# shared_pcb.net
KiCad netlist of a schematic drawn in EAGLE
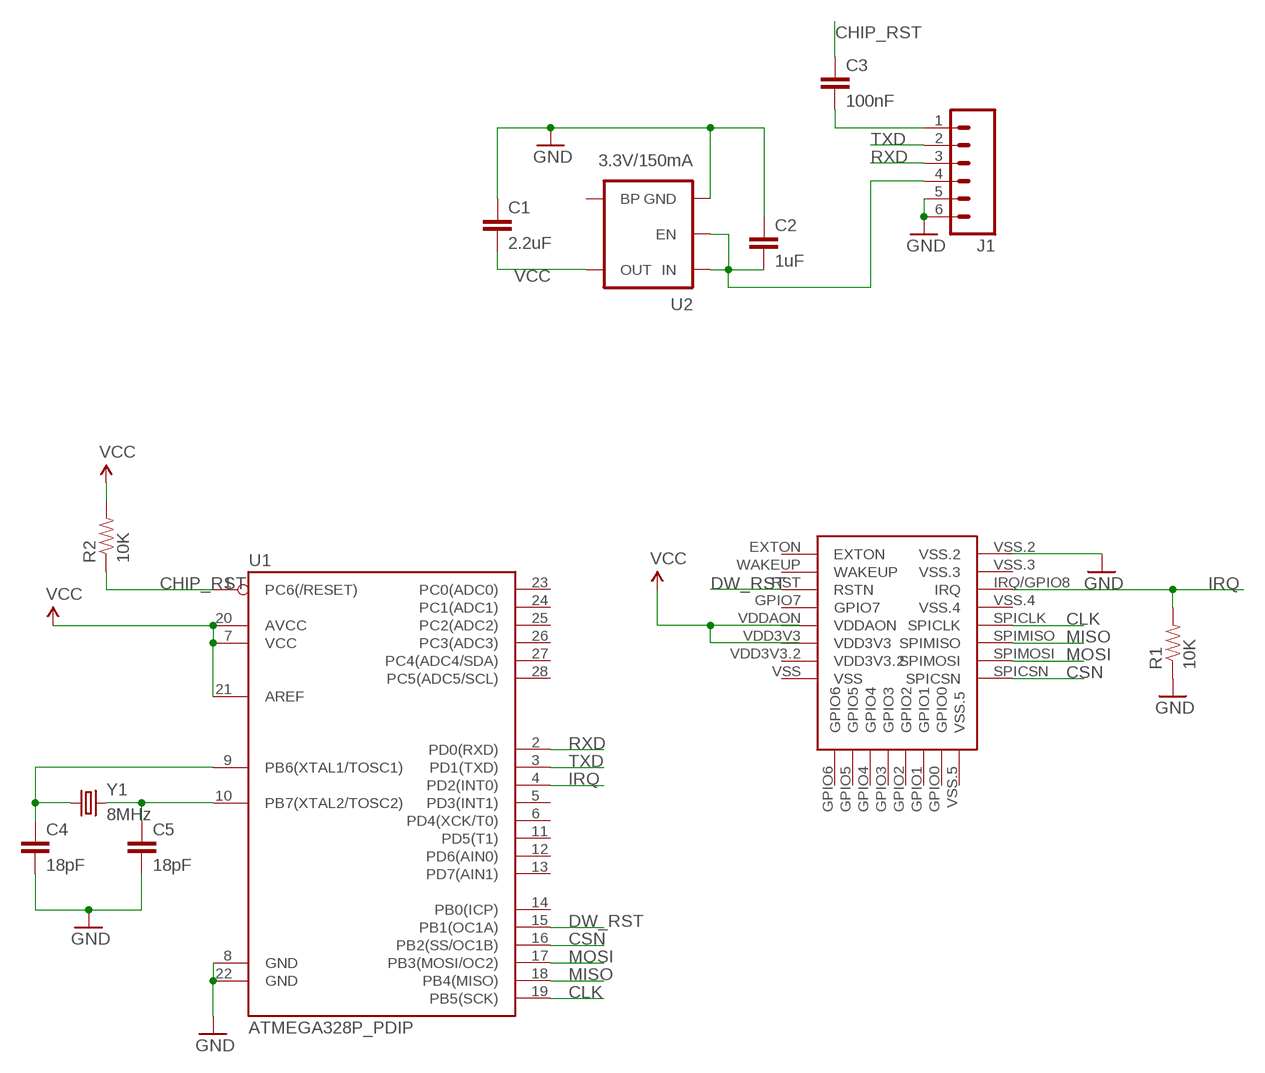
[diagram p0: schematic, sheet 1]

(export (version "E")
  (design (tool "Eeschema 10.0.6"))
  (components
    (comp (ref "C1")
      (value "2.2uF")
      (footprint "eagle-import:1206")
      (libsource (lib "eagle-import") (part "CAP1206"))
    )
    (comp (ref "C2")
      (value "1uF")
      (footprint "eagle-import:1206")
      (libsource (lib "eagle-import") (part "CAP1206"))
    )
    (comp (ref "C3")
      (value "100nF")
      (footprint "eagle-import:1206")
      (libsource (lib "eagle-import") (part "CAP1206"))
    )
    (comp (ref "C4")
      (value "18pF")
      (footprint "eagle-import:1206")
      (libsource (lib "eagle-import") (part "CAP1206"))
    )
    (comp (ref "C5")
      (value "18pF")
      (footprint "eagle-import:1206")
      (libsource (lib "eagle-import") (part "CAP1206"))
    )
    (comp (ref "J1")
      (value "M06LOCK")
      (footprint "eagle-import:1X06_LOCK")
      (libsource (lib "eagle-import") (part "M06LOCK"))
    )
    (comp (ref "R1")
      (value "10K")
      (footprint "eagle-import:1206")
      (libsource (lib "eagle-import") (part "RESISTOR1206"))
    )
    (comp (ref "R2")
      (value "10K")
      (footprint "eagle-import:1206")
      (libsource (lib "eagle-import") (part "RESISTOR1206"))
    )
    (comp (ref "U$1")
      (value "DWM1000")
      (footprint "eagle-import:DWM1000")
      (libsource (lib "eagle-import") (part "DWM1000"))
    )
    (comp (ref "U1")
      (value "ATMEGA328P_PDIP")
      (footprint "eagle-import:DIL28-3")
      (libsource (lib "eagle-import") (part "ATMEGA328P_PDIP"))
    )
    (comp (ref "U2")
      (value "3.3V/150mA")
      (footprint "eagle-import:SOT23-5")
      (libsource (lib "eagle-import") (part "V_REG_MIC52053.3V"))
    )
    (comp (ref "Y1")
      (value "8MHz")
      (footprint "eagle-import:CRYSTAL-TXC-7A")
      (libsource (lib "eagle-import") (part "CRYSTALTXC-7A"))
    )
  )
  (nets
    (net (code "1") (name "/CHIP_RST") (class "Default")
      (node (ref "C3") (pin "1") (pinfunction "1_1") (pintype "passive"))
      (node (ref "R2") (pin "1") (pinfunction "1_1") (pintype "passive"))
      (node (ref "U1") (pin "1") (pinfunction "PC6(/RESET)_1") (pintype "bidirectional"))
    )
    (net (code "2") (name "/CLK") (class "Default")
      (node (ref "U$1") (pin "SPICLK") (pinfunction "SPICLK_SPICLK") (pintype "bidirectional"))
      (node (ref "U1") (pin "19") (pinfunction "PB5(SCK)_19") (pintype "bidirectional"))
    )
    (net (code "3") (name "/CSN") (class "Default")
      (node (ref "U$1") (pin "SPICSN") (pinfunction "SPICSN_SPICSN") (pintype "bidirectional"))
      (node (ref "U1") (pin "16") (pinfunction "PB2(SS/OC1B)_16") (pintype "bidirectional"))
    )
    (net (code "4") (name "/DW_RST") (class "Default")
      (node (ref "U$1") (pin "RST") (pinfunction "RSTN_RST") (pintype "bidirectional"))
      (node (ref "U1") (pin "15") (pinfunction "PB1(OC1A)_15") (pintype "bidirectional"))
    )
    (net (code "5") (name "/IRQ") (class "Default")
      (node (ref "R1") (pin "2") (pinfunction "2_2") (pintype "passive"))
      (node (ref "U$1") (pin "IRQ/GPIO8") (pinfunction "IRQ_IRQ/GPIO8") (pintype "bidirectional"))
      (node (ref "U1") (pin "4") (pinfunction "PD2(INT0)_4") (pintype "bidirectional"))
    )
    (net (code "6") (name "/MISO") (class "Default")
      (node (ref "U$1") (pin "SPIMISO") (pinfunction "SPIMISO_SPIMISO") (pintype "bidirectional"))
      (node (ref "U1") (pin "18") (pinfunction "PB4(MISO)_18") (pintype "bidirectional"))
    )
    (net (code "7") (name "/MOSI") (class "Default")
      (node (ref "U$1") (pin "SPIMOSI") (pinfunction "SPIMOSI_SPIMOSI") (pintype "bidirectional"))
      (node (ref "U1") (pin "17") (pinfunction "PB3(MOSI/OC2)_17") (pintype "bidirectional"))
    )
    (net (code "8") (name "/RXD") (class "Default")
      (node (ref "J1") (pin "3") (pinfunction "3_3") (pintype "passive"))
      (node (ref "U1") (pin "2") (pinfunction "PD0(RXD)_2") (pintype "bidirectional"))
    )
    (net (code "9") (name "/TXD") (class "Default")
      (node (ref "J1") (pin "2") (pinfunction "2_2") (pintype "passive"))
      (node (ref "U1") (pin "3") (pinfunction "PD1(TXD)_3") (pintype "bidirectional"))
    )
    (net (code "10") (name "GND") (class "Default")
      (node (ref "C1") (pin "1") (pinfunction "1_1") (pintype "passive"))
      (node (ref "C2") (pin "1") (pinfunction "1_1") (pintype "passive"))
      (node (ref "C4") (pin "2") (pinfunction "2_2") (pintype "passive"))
      (node (ref "C5") (pin "2") (pinfunction "2_2") (pintype "passive"))
      (node (ref "J1") (pin "5") (pinfunction "5_5") (pintype "passive"))
      (node (ref "J1") (pin "6") (pinfunction "6_6") (pintype "passive"))
      (node (ref "R1") (pin "1") (pinfunction "1_1") (pintype "passive"))
      (node (ref "U$1") (pin "VSS.2") (pinfunction "VSS.2_VSS.2") (pintype "bidirectional"))
      (node (ref "U1") (pin "22") (pinfunction "GND_22") (pintype "bidirectional"))
      (node (ref "U1") (pin "8") (pinfunction "GND_8") (pintype "bidirectional"))
      (node (ref "U2") (pin "2") (pinfunction "GND_2") (pintype "input"))
    )
    (net (code "11") (name "Net-(C3-Pad2)") (class "Default")
      (node (ref "C3") (pin "2") (pinfunction "2_2") (pintype "passive"))
      (node (ref "J1") (pin "1") (pinfunction "1_1") (pintype "passive"))
    )
    (net (code "12") (name "Net-(U1-PB6(XTAL1{slash}TOSC1))") (class "Default")
      (node (ref "C4") (pin "1") (pinfunction "1_1") (pintype "passive"))
      (node (ref "U1") (pin "9") (pinfunction "PB6(XTAL1/TOSC1)_9") (pintype "bidirectional"))
      (node (ref "Y1") (pin "P$1") (pinfunction "1_P$1") (pintype "passive"))
    )
    (net (code "13") (name "Net-(U1-PB7(XTAL2{slash}TOSC2))") (class "Default")
      (node (ref "C5") (pin "1") (pinfunction "1_1") (pintype "passive"))
      (node (ref "U1") (pin "10") (pinfunction "PB7(XTAL2/TOSC2)_10") (pintype "bidirectional"))
      (node (ref "Y1") (pin "P$2") (pinfunction "2_P$2") (pintype "passive"))
    )
    (net (code "14") (name "Net-(U2-EN)") (class "Default")
      (node (ref "C2") (pin "2") (pinfunction "2_2") (pintype "passive"))
      (node (ref "J1") (pin "4") (pinfunction "4_4") (pintype "passive"))
      (node (ref "U2") (pin "1") (pinfunction "IN_1") (pintype "input"))
      (node (ref "U2") (pin "3") (pinfunction "EN_3") (pintype "input"))
    )
    (net (code "15") (name "VCC") (class "Default")
      (node (ref "C1") (pin "2") (pinfunction "2_2") (pintype "passive"))
      (node (ref "R2") (pin "2") (pinfunction "2_2") (pintype "passive"))
      (node (ref "U1") (pin "20") (pinfunction "AVCC_20") (pintype "bidirectional"))
      (node (ref "U1") (pin "21") (pinfunction "AREF_21") (pintype "bidirectional"))
      (node (ref "U1") (pin "7") (pinfunction "VCC_7") (pintype "bidirectional"))
      (node (ref "U2") (pin "5") (pinfunction "OUT_5") (pintype "passive"))
    )
    (net (code "16") (name "unconnected-(U$1-PadEXTON)") (class "Default")
      (node (ref "U$1") (pin "EXTON") (pinfunction "EXTON_EXTON") (pintype "bidirectional"))
    )
    (net (code "17") (name "unconnected-(U$1-PadGPIO0)") (class "Default")
      (node (ref "U$1") (pin "GPIO0") (pinfunction "GPIO0_GPIO0") (pintype "bidirectional"))
    )
    (net (code "18") (name "unconnected-(U$1-PadGPIO1)") (class "Default")
      (node (ref "U$1") (pin "GPIO1") (pinfunction "GPIO1_GPIO1") (pintype "bidirectional"))
    )
    (net (code "19") (name "unconnected-(U$1-PadGPIO2)") (class "Default")
      (node (ref "U$1") (pin "GPIO2") (pinfunction "GPIO2_GPIO2") (pintype "bidirectional"))
    )
    (net (code "20") (name "unconnected-(U$1-PadGPIO3)") (class "Default")
      (node (ref "U$1") (pin "GPIO3") (pinfunction "GPIO3_GPIO3") (pintype "bidirectional"))
    )
    (net (code "21") (name "unconnected-(U$1-PadGPIO4)") (class "Default")
      (node (ref "U$1") (pin "GPIO4") (pinfunction "GPIO4_GPIO4") (pintype "bidirectional"))
    )
    (net (code "22") (name "unconnected-(U$1-PadGPIO5)") (class "Default")
      (node (ref "U$1") (pin "GPIO5") (pinfunction "GPIO5_GPIO5") (pintype "bidirectional"))
    )
    (net (code "23") (name "unconnected-(U$1-PadGPIO6)") (class "Default")
      (node (ref "U$1") (pin "GPIO6") (pinfunction "GPIO6_GPIO6") (pintype "bidirectional"))
    )
    (net (code "24") (name "unconnected-(U$1-PadGPIO7)") (class "Default")
      (node (ref "U$1") (pin "GPIO7") (pinfunction "GPIO7_GPIO7") (pintype "bidirectional"))
    )
    (net (code "25") (name "unconnected-(U$1-PadVDD3V3)") (class "Default")
      (node (ref "U$1") (pin "VDD3V3") (pinfunction "VDD3V3_VDD3V3") (pintype "bidirectional"))
    )
    (net (code "26") (name "unconnected-(U$1-PadVDD3V3.2)") (class "Default")
      (node (ref "U$1") (pin "VDD3V3.2") (pinfunction "VDD3V3.2_VDD3V3.2") (pintype "bidirectional"))
    )
    (net (code "27") (name "unconnected-(U$1-PadVDDAON)") (class "Default")
      (node (ref "U$1") (pin "VDDAON") (pinfunction "VDDAON_VDDAON") (pintype "bidirectional"))
    )
    (net (code "28") (name "unconnected-(U$1-PadVSS)") (class "Default")
      (node (ref "U$1") (pin "VSS") (pinfunction "VSS_VSS") (pintype "bidirectional"))
    )
    (net (code "29") (name "unconnected-(U$1-PadVSS.3)") (class "Default")
      (node (ref "U$1") (pin "VSS.3") (pinfunction "VSS.3_VSS.3") (pintype "bidirectional"))
    )
    (net (code "30") (name "unconnected-(U$1-PadVSS.4)") (class "Default")
      (node (ref "U$1") (pin "VSS.4") (pinfunction "VSS.4_VSS.4") (pintype "bidirectional"))
    )
    (net (code "31") (name "unconnected-(U$1-PadVSS.5)") (class "Default")
      (node (ref "U$1") (pin "VSS.5") (pinfunction "VSS.5_VSS.5") (pintype "bidirectional"))
    )
    (net (code "32") (name "unconnected-(U$1-PadWAKEUP)") (class "Default")
      (node (ref "U$1") (pin "WAKEUP") (pinfunction "WAKEUP_WAKEUP") (pintype "bidirectional"))
    )
    (net (code "33") (name "unconnected-(U1-PB0(ICP)-Pad14)") (class "Default")
      (node (ref "U1") (pin "14") (pinfunction "PB0(ICP)_14") (pintype "bidirectional"))
    )
    (net (code "34") (name "unconnected-(U1-PC0(ADC0)-Pad23)") (class "Default")
      (node (ref "U1") (pin "23") (pinfunction "PC0(ADC0)_23") (pintype "bidirectional"))
    )
    (net (code "35") (name "unconnected-(U1-PC1(ADC1)-Pad24)") (class "Default")
      (node (ref "U1") (pin "24") (pinfunction "PC1(ADC1)_24") (pintype "bidirectional"))
    )
    (net (code "36") (name "unconnected-(U1-PC2(ADC2)-Pad25)") (class "Default")
      (node (ref "U1") (pin "25") (pinfunction "PC2(ADC2)_25") (pintype "bidirectional"))
    )
    (net (code "37") (name "unconnected-(U1-PC3(ADC3)-Pad26)") (class "Default")
      (node (ref "U1") (pin "26") (pinfunction "PC3(ADC3)_26") (pintype "bidirectional"))
    )
    (net (code "38") (name "unconnected-(U1-PC4(ADC4{slash}SDA)-Pad27)") (class "Default")
      (node (ref "U1") (pin "27") (pinfunction "PC4(ADC4/SDA)_27") (pintype "bidirectional"))
    )
    (net (code "39") (name "unconnected-(U1-PC5(ADC5{slash}SCL)-Pad28)") (class "Default")
      (node (ref "U1") (pin "28") (pinfunction "PC5(ADC5/SCL)_28") (pintype "bidirectional"))
    )
    (net (code "40") (name "unconnected-(U1-PD3(INT1)-Pad5)") (class "Default")
      (node (ref "U1") (pin "5") (pinfunction "PD3(INT1)_5") (pintype "bidirectional"))
    )
    (net (code "41") (name "unconnected-(U1-PD4(XCK{slash}T0)-Pad6)") (class "Default")
      (node (ref "U1") (pin "6") (pinfunction "PD4(XCK/T0)_6") (pintype "bidirectional"))
    )
    (net (code "42") (name "unconnected-(U1-PD5(T1)-Pad11)") (class "Default")
      (node (ref "U1") (pin "11") (pinfunction "PD5(T1)_11") (pintype "bidirectional"))
    )
    (net (code "43") (name "unconnected-(U1-PD6(AIN0)-Pad12)") (class "Default")
      (node (ref "U1") (pin "12") (pinfunction "PD6(AIN0)_12") (pintype "bidirectional"))
    )
    (net (code "44") (name "unconnected-(U1-PD7(AIN1)-Pad13)") (class "Default")
      (node (ref "U1") (pin "13") (pinfunction "PD7(AIN1)_13") (pintype "bidirectional"))
    )
    (net (code "45") (name "unconnected-(U2-BP-Pad4)") (class "Default")
      (node (ref "U2") (pin "4") (pinfunction "BP_4") (pintype "input"))
    )
  )
)
